# power_boardv2.net
KiCad netlist of a schematic drawn in EAGLE
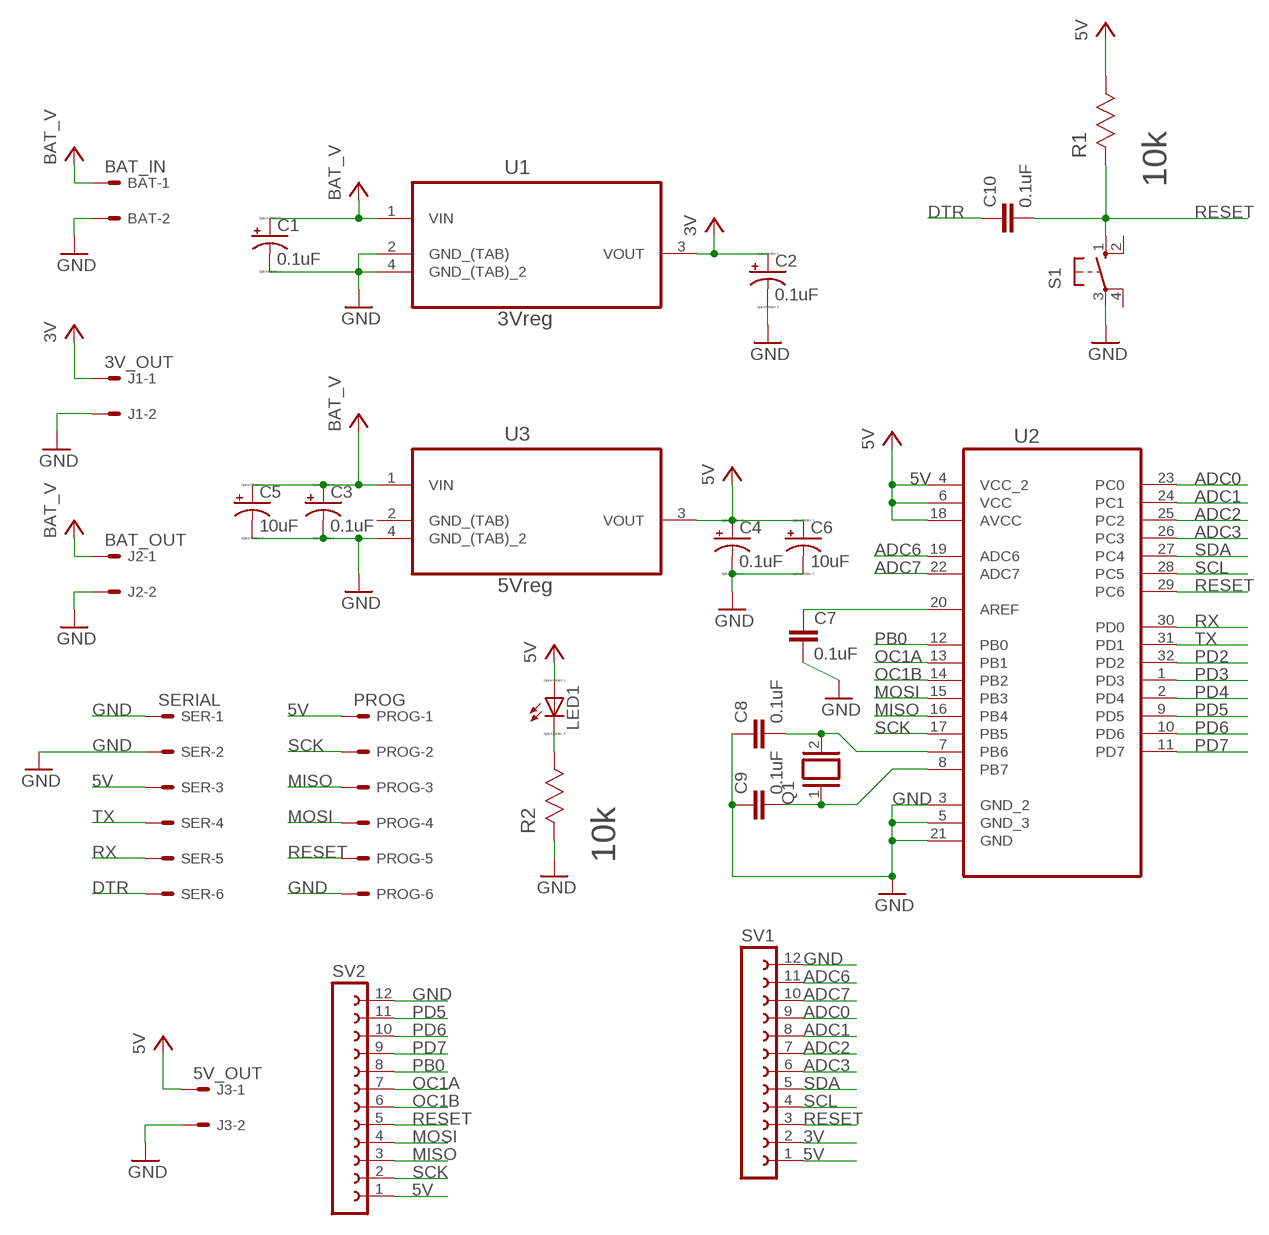
[diagram p0: schematic, sheet 1]

(export (version "E")
  (design (tool "Eeschema 10.0.6"))
  (components
    (comp (ref "BAT")
      (value "BAT_IN")
      (footprint "eagle-import:7395-02")
      (libsource (lib "eagle-import") (part "22-?-0205-7028"))
    )
    (comp (ref "C1")
      (value "0.1uF")
      (footprint "eagle-import:E2,5-5")
      (libsource (lib "eagle-import") (part "CPOL-USE2.5-5"))
    )
    (comp (ref "C2")
      (value "0.1uF")
      (footprint "eagle-import:E2,5-5")
      (libsource (lib "eagle-import") (part "CPOL-USE2.5-5"))
    )
    (comp (ref "C3")
      (value "0.1uF")
      (footprint "eagle-import:E2,5-5")
      (libsource (lib "eagle-import") (part "CPOL-USE2.5-5"))
    )
    (comp (ref "C4")
      (value "0.1uF")
      (footprint "eagle-import:E2,5-5")
      (libsource (lib "eagle-import") (part "CPOL-USE2.5-5"))
    )
    (comp (ref "C5")
      (value "10uF")
      (footprint "eagle-import:E2,5-5")
      (libsource (lib "eagle-import") (part "CPOL-USE2.5-5"))
    )
    (comp (ref "C6")
      (value "10uF")
      (footprint "eagle-import:E2,5-5")
      (libsource (lib "eagle-import") (part "CPOL-USE2.5-5"))
    )
    (comp (ref "C7")
      (value "0.1uF")
      (footprint "eagle-import:C2.5-3")
      (libsource (lib "eagle-import") (part "C2,5-3"))
    )
    (comp (ref "C8")
      (value "0.1uF")
      (footprint "eagle-import:C2.5-3")
      (libsource (lib "eagle-import") (part "C2,5-3"))
    )
    (comp (ref "C9")
      (value "0.1uF")
      (footprint "eagle-import:C2.5-3")
      (libsource (lib "eagle-import") (part "C2,5-3"))
    )
    (comp (ref "C10")
      (value "0.1uF")
      (footprint "eagle-import:C2.5-3")
      (libsource (lib "eagle-import") (part "C2,5-3"))
    )
    (comp (ref "J1")
      (value "3V_OUT")
      (footprint "eagle-import:7395-02")
      (libsource (lib "eagle-import") (part "22-?-0205-7028"))
    )
    (comp (ref "J2")
      (value "BAT_OUT")
      (footprint "eagle-import:7395-02")
      (libsource (lib "eagle-import") (part "22-?-0205-7028"))
    )
    (comp (ref "J3")
      (value "5V_OUT")
      (footprint "eagle-import:7395-02")
      (libsource (lib "eagle-import") (part "22-?-0205-7028"))
    )
    (comp (ref "LED1")
      (value "LED_E")
      (footprint "eagle-import:LED_1206")
      (libsource (lib "eagle-import") (part "LED_E"))
    )
    (comp (ref "PROG")
      (value "PROG")
      (footprint "eagle-import:7395-06")
      (libsource (lib "eagle-import") (part "22-?-0605-7068"))
    )
    (comp (ref "Q1")
      (value "XTAL/S")
      (footprint "eagle-import:QS")
      (libsource (lib "eagle-import") (part "XTAL/S"))
    )
    (comp (ref "R1")
      (value "10k")
      (footprint "eagle-import:RESC2013X65N")
      (fields (field (name "MPN") "CRCW08051M00JNEA") (field (name "TOLERANCE") "± 5.0 %"))
      (libsource (lib "eagle-import") (part "CRCW08051M00JNEA"))
    )
    (comp (ref "R2")
      (value "10k")
      (footprint "eagle-import:RESC2013X65N")
      (fields (field (name "MPN") "CRCW08051M00JNEA") (field (name "TOLERANCE") "± 5.0 %"))
      (libsource (lib "eagle-import") (part "CRCW08051M00JNEA"))
    )
    (comp (ref "S1")
      (value "10-XX")
      (footprint "eagle-import:B3F-10XX")
      (fields (field (name "MPN") "B3F-1000"))
      (libsource (lib "eagle-import") (part "10-XX"))
    )
    (comp (ref "SER")
      (value "SERIAL")
      (footprint "eagle-import:7395-06")
      (libsource (lib "eagle-import") (part "22-?-0605-7068"))
    )
    (comp (ref "SV1")
      (value "FE12-1")
      (footprint "eagle-import:FE12")
      (libsource (lib "eagle-import") (part "FE12-1"))
    )
    (comp (ref "SV2")
      (value "FE12-1")
      (footprint "eagle-import:FE12")
      (libsource (lib "eagle-import") (part "FE12-1"))
    )
    (comp (ref "U1")
      (value "3Vreg")
      (footprint "eagle-import:SOT230P700X180-4N")
      (fields (field (name "MPN") "MCP1826S-3302E/DB"))
      (libsource (lib "eagle-import") (part "MCP1826S-3302E/DB"))
    )
    (comp (ref "U2")
      (value "ATMEGA328P-AU")
      (footprint "eagle-import:QFP80P900X900X120-32N")
      (libsource (lib "eagle-import") (part "ATMEGA328P-AU"))
    )
    (comp (ref "U3")
      (value "5Vreg")
      (footprint "eagle-import:SOT230P700X180-4N")
      (fields (field (name "MPN") "MCP1824ST-5002E/DB"))
      (libsource (lib "eagle-import") (part "MCP1824ST-5002E/DB"))
    )
  )
  (nets
    (net (code "1") (name "/ADC0") (class "Default")
      (node (ref "SV1") (pin "9") (pinfunction "9_9") (pintype "passive"))
      (node (ref "U2") (pin "23") (pinfunction "PC0_23") (pintype "bidirectional"))
    )
    (net (code "2") (name "/ADC1") (class "Default")
      (node (ref "SV1") (pin "8") (pinfunction "8_8") (pintype "passive"))
      (node (ref "U2") (pin "24") (pinfunction "PC1_24") (pintype "bidirectional"))
    )
    (net (code "3") (name "/ADC2") (class "Default")
      (node (ref "SV1") (pin "7") (pinfunction "7_7") (pintype "passive"))
      (node (ref "U2") (pin "25") (pinfunction "PC2_25") (pintype "bidirectional"))
    )
    (net (code "4") (name "/ADC3") (class "Default")
      (node (ref "SV1") (pin "6") (pinfunction "6_6") (pintype "passive"))
      (node (ref "U2") (pin "26") (pinfunction "PC3_26") (pintype "bidirectional"))
    )
    (net (code "5") (name "/ADC6") (class "Default")
      (node (ref "SV1") (pin "11") (pinfunction "11_11") (pintype "passive"))
      (node (ref "U2") (pin "19") (pinfunction "ADC6_19") (pintype "input"))
    )
    (net (code "6") (name "/ADC7") (class "Default")
      (node (ref "SV1") (pin "10") (pinfunction "10_10") (pintype "passive"))
      (node (ref "U2") (pin "22") (pinfunction "ADC7_22") (pintype "input"))
    )
    (net (code "7") (name "/DTR") (class "Default")
      (node (ref "C10") (pin "1") (pinfunction "1_1") (pintype "passive"))
      (node (ref "SER") (pin "6") (pinfunction "S_6") (pintype "passive"))
    )
    (net (code "8") (name "/MISO") (class "Default")
      (node (ref "PROG") (pin "3") (pinfunction "S_3") (pintype "passive"))
      (node (ref "SV2") (pin "3") (pinfunction "3_3") (pintype "passive"))
      (node (ref "U2") (pin "16") (pinfunction "PB4_16") (pintype "bidirectional"))
    )
    (net (code "9") (name "/MOSI") (class "Default")
      (node (ref "PROG") (pin "4") (pinfunction "S_4") (pintype "passive"))
      (node (ref "SV2") (pin "4") (pinfunction "4_4") (pintype "passive"))
      (node (ref "U2") (pin "15") (pinfunction "PB3_15") (pintype "bidirectional"))
    )
    (net (code "10") (name "/OC1A") (class "Default")
      (node (ref "SV2") (pin "7") (pinfunction "7_7") (pintype "passive"))
      (node (ref "U2") (pin "13") (pinfunction "PB1_13") (pintype "bidirectional"))
    )
    (net (code "11") (name "/OC1B") (class "Default")
      (node (ref "SV2") (pin "6") (pinfunction "6_6") (pintype "passive"))
      (node (ref "U2") (pin "14") (pinfunction "PB2_14") (pintype "bidirectional"))
    )
    (net (code "12") (name "/PB0") (class "Default")
      (node (ref "SV2") (pin "8") (pinfunction "8_8") (pintype "passive"))
      (node (ref "U2") (pin "12") (pinfunction "PB0_12") (pintype "bidirectional"))
    )
    (net (code "13") (name "/PD2") (class "Default")
      (node (ref "U2") (pin "32") (pinfunction "PD2_32") (pintype "bidirectional"))
    )
    (net (code "14") (name "/PD3") (class "Default")
      (node (ref "U2") (pin "1") (pinfunction "PD3_1") (pintype "bidirectional"))
    )
    (net (code "15") (name "/PD4") (class "Default")
      (node (ref "U2") (pin "2") (pinfunction "PD4_2") (pintype "bidirectional"))
    )
    (net (code "16") (name "/PD5") (class "Default")
      (node (ref "SV2") (pin "11") (pinfunction "11_11") (pintype "passive"))
      (node (ref "U2") (pin "9") (pinfunction "PD5_9") (pintype "bidirectional"))
    )
    (net (code "17") (name "/PD6") (class "Default")
      (node (ref "SV2") (pin "10") (pinfunction "10_10") (pintype "passive"))
      (node (ref "U2") (pin "10") (pinfunction "PD6_10") (pintype "bidirectional"))
    )
    (net (code "18") (name "/PD7") (class "Default")
      (node (ref "SV2") (pin "9") (pinfunction "9_9") (pintype "passive"))
      (node (ref "U2") (pin "11") (pinfunction "PD7_11") (pintype "bidirectional"))
    )
    (net (code "19") (name "/RESET") (class "Default")
      (node (ref "C10") (pin "2") (pinfunction "2_2") (pintype "passive"))
      (node (ref "PROG") (pin "5") (pinfunction "S_5") (pintype "passive"))
      (node (ref "R1") (pin "2") (pinfunction "2_2") (pintype "passive"))
      (node (ref "S1") (pin "1") (pinfunction "S_1") (pintype "passive"))
      (node (ref "SV1") (pin "3") (pinfunction "3_3") (pintype "passive"))
      (node (ref "SV2") (pin "5") (pinfunction "5_5") (pintype "passive"))
      (node (ref "U2") (pin "29") (pinfunction "PC6_29") (pintype "bidirectional"))
    )
    (net (code "20") (name "/RX") (class "Default")
      (node (ref "SER") (pin "5") (pinfunction "S_5") (pintype "passive"))
      (node (ref "U2") (pin "30") (pinfunction "PD0_30") (pintype "bidirectional"))
    )
    (net (code "21") (name "/SCK") (class "Default")
      (node (ref "PROG") (pin "2") (pinfunction "S_2") (pintype "passive"))
      (node (ref "SV2") (pin "2") (pinfunction "2_2") (pintype "passive"))
      (node (ref "U2") (pin "17") (pinfunction "PB5_17") (pintype "bidirectional"))
    )
    (net (code "22") (name "/SCL") (class "Default")
      (node (ref "SV1") (pin "4") (pinfunction "4_4") (pintype "passive"))
      (node (ref "U2") (pin "28") (pinfunction "PC5_28") (pintype "bidirectional"))
    )
    (net (code "23") (name "/SDA") (class "Default")
      (node (ref "SV1") (pin "5") (pinfunction "5_5") (pintype "passive"))
      (node (ref "U2") (pin "27") (pinfunction "PC4_27") (pintype "bidirectional"))
    )
    (net (code "24") (name "/TX") (class "Default")
      (node (ref "SER") (pin "4") (pinfunction "S_4") (pintype "passive"))
      (node (ref "U2") (pin "31") (pinfunction "PD1_31") (pintype "bidirectional"))
    )
    (net (code "25") (name "3V") (class "Default")
      (node (ref "C2") (pin "+") (pinfunction "+_+") (pintype "passive"))
      (node (ref "J1") (pin "1") (pinfunction "S_1") (pintype "passive"))
      (node (ref "SV1") (pin "2") (pinfunction "2_2") (pintype "passive"))
      (node (ref "U1") (pin "3") (pinfunction "VOUT_3") (pintype "output"))
    )
    (net (code "26") (name "5V") (class "Default")
      (node (ref "C4") (pin "+") (pinfunction "+_+") (pintype "passive"))
      (node (ref "C6") (pin "+") (pinfunction "+_+") (pintype "passive"))
      (node (ref "J3") (pin "1") (pinfunction "S_1") (pintype "passive"))
      (node (ref "LED1") (pin "A") (pinfunction "A_A") (pintype "passive"))
      (node (ref "PROG") (pin "1") (pinfunction "S_1") (pintype "passive"))
      (node (ref "R1") (pin "1") (pinfunction "1_1") (pintype "passive"))
      (node (ref "SER") (pin "3") (pinfunction "S_3") (pintype "passive"))
      (node (ref "SV1") (pin "1") (pinfunction "1_1") (pintype "passive"))
      (node (ref "SV2") (pin "1") (pinfunction "1_1") (pintype "passive"))
      (node (ref "U2") (pin "18") (pinfunction "AVCC_18") (pintype "power_in"))
      (node (ref "U2") (pin "4") (pinfunction "VCC_2_4") (pintype "power_in"))
      (node (ref "U2") (pin "6") (pinfunction "VCC_6") (pintype "power_in"))
      (node (ref "U3") (pin "3") (pinfunction "VOUT_3") (pintype "output"))
    )
    (net (code "27") (name "BAT_V") (class "Default")
      (node (ref "BAT") (pin "1") (pinfunction "S_1") (pintype "passive"))
      (node (ref "C1") (pin "+") (pinfunction "+_+") (pintype "passive"))
      (node (ref "C3") (pin "+") (pinfunction "+_+") (pintype "passive"))
      (node (ref "C5") (pin "+") (pinfunction "+_+") (pintype "passive"))
      (node (ref "J2") (pin "1") (pinfunction "S_1") (pintype "passive"))
      (node (ref "U1") (pin "1") (pinfunction "VIN_1") (pintype "input"))
      (node (ref "U3") (pin "1") (pinfunction "VIN_1") (pintype "input"))
    )
    (net (code "28") (name "GND") (class "Default")
      (node (ref "BAT") (pin "2") (pinfunction "S_2") (pintype "passive"))
      (node (ref "C1") (pin "-") (pinfunction "-_-") (pintype "passive"))
      (node (ref "C2") (pin "-") (pinfunction "-_-") (pintype "passive"))
      (node (ref "C3") (pin "-") (pinfunction "-_-") (pintype "passive"))
      (node (ref "C4") (pin "-") (pinfunction "-_-") (pintype "passive"))
      (node (ref "C5") (pin "-") (pinfunction "-_-") (pintype "passive"))
      (node (ref "C6") (pin "-") (pinfunction "-_-") (pintype "passive"))
      (node (ref "C7") (pin "2") (pinfunction "2_2") (pintype "passive"))
      (node (ref "C8") (pin "1") (pinfunction "1_1") (pintype "passive"))
      (node (ref "C9") (pin "1") (pinfunction "1_1") (pintype "passive"))
      (node (ref "J1") (pin "2") (pinfunction "S_2") (pintype "passive"))
      (node (ref "J2") (pin "2") (pinfunction "S_2") (pintype "passive"))
      (node (ref "J3") (pin "2") (pinfunction "S_2") (pintype "passive"))
      (node (ref "PROG") (pin "6") (pinfunction "S_6") (pintype "passive"))
      (node (ref "R2") (pin "2") (pinfunction "2_2") (pintype "passive"))
      (node (ref "S1") (pin "3") (pinfunction "P_3") (pintype "passive"))
      (node (ref "SER") (pin "1") (pinfunction "S_1") (pintype "passive"))
      (node (ref "SER") (pin "2") (pinfunction "S_2") (pintype "passive"))
      (node (ref "SV1") (pin "12") (pinfunction "12_12") (pintype "passive"))
      (node (ref "SV2") (pin "12") (pinfunction "12_12") (pintype "passive"))
      (node (ref "U1") (pin "2") (pinfunction "GND_(TAB)_2") (pintype "passive"))
      (node (ref "U1") (pin "4") (pinfunction "GND_(TAB)_2_4") (pintype "passive"))
      (node (ref "U2") (pin "21") (pinfunction "GND_21") (pintype "passive"))
      (node (ref "U2") (pin "3") (pinfunction "GND_2_3") (pintype "passive"))
      (node (ref "U2") (pin "5") (pinfunction "GND_3_5") (pintype "passive"))
      (node (ref "U3") (pin "4") (pinfunction "GND_(TAB)_2_4") (pintype "passive"))
    )
    (net (code "29") (name "Net-(LED1-PadC)") (class "Default")
      (node (ref "LED1") (pin "C") (pinfunction "C_C") (pintype "passive"))
      (node (ref "R2") (pin "1") (pinfunction "1_1") (pintype "passive"))
    )
    (net (code "30") (name "Net-(U2-AREF)") (class "Default")
      (node (ref "C7") (pin "1") (pinfunction "1_1") (pintype "passive"))
      (node (ref "U2") (pin "20") (pinfunction "AREF_20") (pintype "input"))
    )
    (net (code "31") (name "Net-(U2-PB6)") (class "Default")
      (node (ref "C8") (pin "2") (pinfunction "2_2") (pintype "passive"))
      (node (ref "Q1") (pin "2") (pinfunction "2_2") (pintype "passive"))
      (node (ref "U2") (pin "7") (pinfunction "PB6_7") (pintype "bidirectional"))
    )
    (net (code "32") (name "Net-(U2-PB7)") (class "Default")
      (node (ref "C9") (pin "2") (pinfunction "2_2") (pintype "passive"))
      (node (ref "Q1") (pin "1") (pinfunction "1_1") (pintype "passive"))
      (node (ref "U2") (pin "8") (pinfunction "PB7_8") (pintype "bidirectional"))
    )
    (net (code "33") (name "unconnected-(S1-P1-Pad4)") (class "Default")
      (node (ref "S1") (pin "4") (pinfunction "P1_4") (pintype "passive"))
    )
    (net (code "34") (name "unconnected-(S1-S1-Pad2)") (class "Default")
      (node (ref "S1") (pin "2") (pinfunction "S1_2") (pintype "passive"))
    )
    (net (code "35") (name "unconnected-(U3-GND_(TAB)-Pad2)") (class "Default")
      (node (ref "U3") (pin "2") (pinfunction "GND_(TAB)_2") (pintype "passive"))
    )
  )
)
